# door_lock_controller.net
KiCad netlist of a schematic drawn in Altium Designer
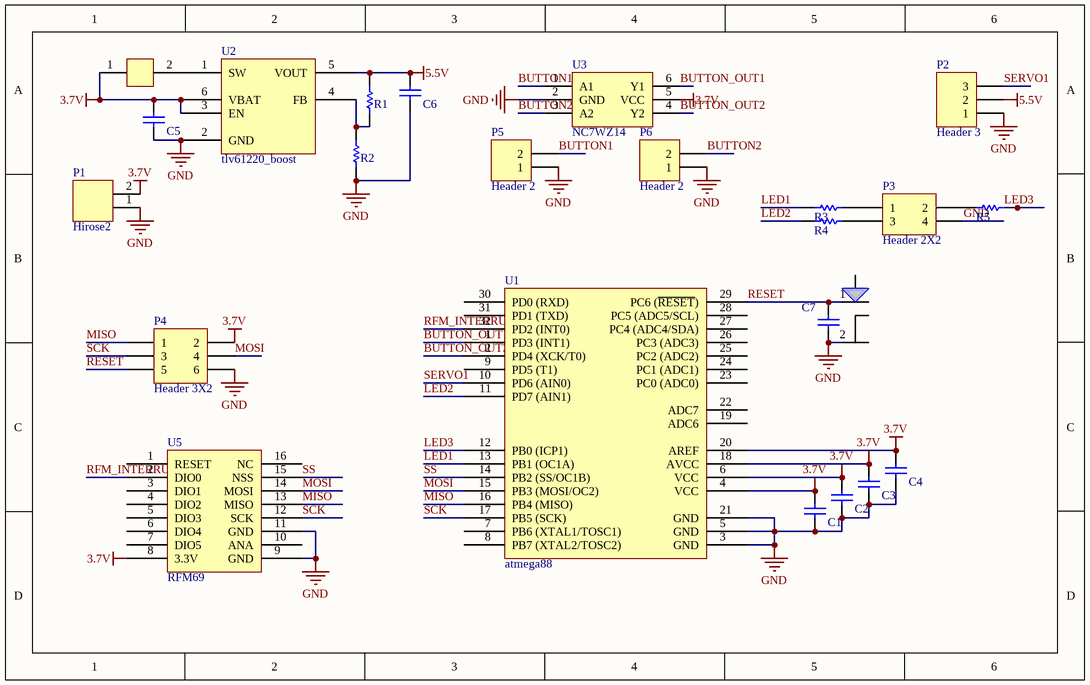
[diagram p0: door_lock_controller.SchDoc]

(export (version "E")
  (design (tool "Eeschema 10.0.6"))
  (components
    (comp (ref "C1")
      (value "CAP 100nF 10V 0603(1608)")
      (footprint "CAPC0603(1608)100_N")
      (description "CAP 100nF 10V ±20% 0603 (1608 Metric) Thickness 1mm SMD")
      (fields (field (name "TOLERANCE") "±20%"))
      (libsource (lib "Altium Content Vault") (part "CMP-1035-02581-1"))
    )
    (comp (ref "C2")
      (value "CAP 100nF 10V 0603(1608)")
      (footprint "CAPC0603(1608)100_N")
      (description "CAP 100nF 10V ±20% 0603 (1608 Metric) Thickness 1mm SMD")
      (fields (field (name "TOLERANCE") "±20%"))
      (libsource (lib "Altium Content Vault") (part "CMP-1035-02581-1"))
    )
    (comp (ref "C3")
      (value "CAP 100nF 10V 0603(1608)")
      (footprint "CAPC0603(1608)100_N")
      (description "CAP 100nF 10V ±20% 0603 (1608 Metric) Thickness 1mm SMD")
      (fields (field (name "TOLERANCE") "±20%"))
      (libsource (lib "Altium Content Vault") (part "CMP-1035-02581-1"))
    )
    (comp (ref "C4")
      (value "CAP 100nF 10V 0603(1608)")
      (footprint "CAPC0603(1608)100_N")
      (description "CAP 100nF 10V ±20% 0603 (1608 Metric) Thickness 1mm SMD")
      (fields (field (name "TOLERANCE") "±20%"))
      (libsource (lib "Altium Content Vault") (part "CMP-1035-02581-1"))
    )
    (comp (ref "C5")
      (value "CAP 10uF 10V 0603(1608)")
      (footprint "CAPC0603(1608)100_N")
      (description "CAP 10uF 10V ±10% 0603 (1608 Metric) Thickness 1mm SMD")
      (fields (field (name "TOLERANCE") "±10%"))
      (libsource (lib "Altium Content Vault") (part "CMP-1035-02799-1"))
    )
    (comp (ref "C6")
      (value "CAP 10uF 10V 0603(1608)")
      (footprint "CAPC0603(1608)100_N")
      (description "CAP 10uF 10V ±10% 0603 (1608 Metric) Thickness 1mm SMD")
      (fields (field (name "TOLERANCE") "±10%"))
      (libsource (lib "Altium Content Vault") (part "CMP-1035-02799-1"))
    )
    (comp (ref "C7")
      (value "CAP 10nF 10V 0603(1608)")
      (footprint "CAPC0603(1608)100_M")
      (description "CAP 10nF 10V ±2% 0603 (1608 Metric) Thickness 1mm SMD")
      (fields (field (name "TOLERANCE") "±2%"))
      (libsource (lib "Altium Content Vault") (part "CMP-1035-02304-1"))
    )
    (comp (ref "L1")
      (value "TYS6045_inductor")
      (footprint "TYS6045")
      (libsource (lib "Integrated_Library") (part "TYS6045_inductor"))
    )
    (comp (ref "P1")
      (value "Hirose2")
      (footprint "DF3A-2P-2DS")
      (libsource (lib "Integrated_Library") (part "Hirose2"))
    )
    (comp (ref "P2")
      (value "Header 3")
      (footprint "HDR1X3")
      (description "Header, 3-Pin")
      (fields (field (name "PUBLISHER") "Altium Limited"))
      (libsource (lib "Miscellaneous Connectors") (part "Header 3"))
    )
    (comp (ref "P3")
      (value "Header 2X2")
      (footprint "HDR2X2")
      (description "Header, 2-Pin, Dual row")
      (fields (field (name "PUBLISHER") "Altium Limited"))
      (libsource (lib "Miscellaneous Connectors") (part "Header 2X2"))
    )
    (comp (ref "P4")
      (value "Header 3X2")
      (footprint "HDR2X3")
      (description "Header, 3-Pin, Dual row")
      (fields (field (name "PUBLISHER") "Altium Limited"))
      (libsource (lib "Miscellaneous Connectors") (part "Header 3X2"))
    )
    (comp (ref "P5")
      (value "Header 2")
      (footprint "HDR1X2")
      (description "Header, 2-Pin")
      (fields (field (name "PUBLISHER") "Altium Limited"))
      (libsource (lib "Miscellaneous Connectors") (part "Header 2"))
    )
    (comp (ref "P6")
      (value "Header 2")
      (footprint "HDR1X2")
      (description "Header, 2-Pin")
      (fields (field (name "PUBLISHER") "Altium Limited"))
      (libsource (lib "Miscellaneous Connectors") (part "Header 2"))
    )
    (comp (ref "R1")
      (value "1M8 5% 0603(1608)")
      (footprint "RESC0603(1608)_L")
      (description "1M8 0.1W 5% 0603 (1608 Metric)  SMD")
      (fields (field (name "TOLERANCE") "5 %") (field (name "POWER") "0.1 W"))
      (libsource (lib "Altium Content Vault") (part "CMP-1012-00152-1"))
    )
    (comp (ref "R2")
      (value "180K 5% 0603(1608)")
      (footprint "RESC0603(1608)_L")
      (description "180K 0.1W 5% 0603 (1608 Metric)  SMD")
      (fields (field (name "POWER") "0.1 W") (field (name "TOLERANCE") "5 %"))
      (libsource (lib "Altium Content Vault") (part "CMP-1012-00128-1"))
    )
    (comp (ref "R3")
      (value "180R 5% 0603(1608)")
      (footprint "RESC0603(1608)_L")
      (description "180R 0.1W 5% 0603 (1608 Metric)  SMD")
      (fields (field (name "POWER") "0.1 W") (field (name "TOLERANCE") "5 %"))
      (libsource (lib "Altium Content Vault") (part "CMP-1012-00056-1"))
    )
    (comp (ref "R4")
      (value "180R 5% 0603(1608)")
      (footprint "RESC0603(1608)_L")
      (description "180R 0.1W 5% 0603 (1608 Metric)  SMD")
      (fields (field (name "POWER") "0.1 W") (field (name "TOLERANCE") "5 %"))
      (libsource (lib "Altium Content Vault") (part "CMP-1012-00056-1"))
    )
    (comp (ref "R5")
      (value "180R 5% 0603(1608)")
      (footprint "RESC0603(1608)_L")
      (description "180R 0.1W 5% 0603 (1608 Metric)  SMD")
      (fields (field (name "POWER") "0.1 W") (field (name "TOLERANCE") "5 %"))
      (libsource (lib "Altium Content Vault") (part "CMP-1012-00056-1"))
    )
    (comp (ref "S1")
      (value "2lead_low_profile_switch")
      (footprint "2lead_low_profile_switch")
      (libsource (lib "Integrated_Library") (part "2lead_low_profile_switch"))
    )
    (comp (ref "U1")
      (value "atmega88")
      (footprint "atmega44/88/168")
      (libsource (lib "Integrated_Library") (part "atmega88"))
    )
    (comp (ref "U2")
      (value "tlv61220_boost")
      (footprint "TLV61220_BOOST")
      (libsource (lib "Integrated_Library") (part "tlv61220_boost"))
    )
    (comp (ref "U3")
      (value "NC7WZ14")
      (footprint "NC7WZ14")
      (libsource (lib "Integrated_Library") (part "NC7WZ14"))
    )
    (comp (ref "U5")
      (value "RFM69")
      (footprint "RFM69")
      (libsource (lib "Integrated_Library") (part "RFM69"))
    )
  )
  (nets
    (net (code "1") (name "/BUTTON1") (class "Default")
      (node (ref "P5") (pin "2") (pinfunction "2_2") (pintype "passive"))
      (node (ref "U3") (pin "1") (pinfunction "A1_1") (pintype "passive"))
    )
    (net (code "2") (name "/BUTTON2") (class "Default")
      (node (ref "P6") (pin "2") (pinfunction "2_2") (pintype "passive"))
      (node (ref "U3") (pin "3") (pinfunction "A2_3") (pintype "passive"))
    )
    (net (code "3") (name "/BUTTON_OUT1") (class "Default")
      (node (ref "U1") (pin "1") (pinfunction "PD3_(INT1)_1") (pintype "passive"))
      (node (ref "U3") (pin "6") (pinfunction "Y1_6") (pintype "passive"))
    )
    (net (code "4") (name "/BUTTON_OUT2") (class "Default")
      (node (ref "U1") (pin "2") (pinfunction "PD4_(XCK/T0)_2") (pintype "passive"))
      (node (ref "U3") (pin "4") (pinfunction "Y2_4") (pintype "passive"))
    )
    (net (code "5") (name "/LED1") (class "Default")
      (node (ref "R3") (pin "1") (pinfunction "1_1") (pintype "passive"))
      (node (ref "U1") (pin "13") (pinfunction "PB1_(OC1A)_13") (pintype "passive"))
    )
    (net (code "6") (name "/LED2") (class "Default")
      (node (ref "R4") (pin "1") (pinfunction "1_1") (pintype "passive"))
      (node (ref "U1") (pin "11") (pinfunction "PD7_(AIN1)_11") (pintype "passive"))
    )
    (net (code "7") (name "/LED3") (class "Default")
      (node (ref "R5") (pin "2") (pinfunction "2_2") (pintype "passive"))
      (node (ref "U1") (pin "12") (pinfunction "PB0_(ICP1)_12") (pintype "passive"))
    )
    (net (code "8") (name "/MISO") (class "Default")
      (node (ref "P4") (pin "1") (pinfunction "1_1") (pintype "passive"))
      (node (ref "U1") (pin "16") (pinfunction "PB4_(MISO)_16") (pintype "passive"))
      (node (ref "U5") (pin "13") (pinfunction "MISO_13") (pintype "passive"))
    )
    (net (code "9") (name "/MOSI") (class "Default")
      (node (ref "P4") (pin "4") (pinfunction "4_4") (pintype "passive"))
      (node (ref "U1") (pin "15") (pinfunction "PB3_(MOSI/OC2)_15") (pintype "passive"))
      (node (ref "U5") (pin "14") (pinfunction "MOSI_14") (pintype "passive"))
    )
    (net (code "10") (name "/RESET") (class "Default")
      (node (ref "C7") (pin "2") (pinfunction "2_2") (pintype "passive"))
      (node (ref "P4") (pin "5") (pinfunction "5_5") (pintype "passive"))
      (node (ref "S1") (pin "1") (pinfunction "GND_1") (pintype "passive"))
      (node (ref "U1") (pin "29") (pinfunction "PC6_(~{RESET})_29") (pintype "passive"))
    )
    (net (code "11") (name "/RFM_INTERRUPT") (class "Default")
      (node (ref "U1") (pin "32") (pinfunction "PD2_(INT0)_32") (pintype "passive"))
      (node (ref "U5") (pin "2") (pinfunction "DIO0_2") (pintype "passive"))
    )
    (net (code "12") (name "/SCK") (class "Default")
      (node (ref "P4") (pin "3") (pinfunction "3_3") (pintype "passive"))
      (node (ref "U1") (pin "17") (pinfunction "PB5_(SCK)_17") (pintype "passive"))
      (node (ref "U5") (pin "12") (pinfunction "SCK_12") (pintype "passive"))
    )
    (net (code "13") (name "/SERVO1") (class "Default")
      (node (ref "P2") (pin "3") (pinfunction "3_3") (pintype "passive"))
      (node (ref "U1") (pin "10") (pinfunction "PD6_(AIN0)_10") (pintype "passive"))
    )
    (net (code "14") (name "/SS") (class "Default")
      (node (ref "U1") (pin "14") (pinfunction "PB2_(SS/OC1B)_14") (pintype "passive"))
      (node (ref "U5") (pin "15") (pinfunction "NSS_15") (pintype "passive"))
    )
    (net (code "15") (name "3.7V") (class "Default")
      (node (ref "C1") (pin "2") (pinfunction "2_2") (pintype "passive"))
      (node (ref "C2") (pin "2") (pinfunction "2_2") (pintype "passive"))
      (node (ref "C3") (pin "2") (pinfunction "2_2") (pintype "passive"))
      (node (ref "C4") (pin "2") (pinfunction "2_2") (pintype "passive"))
      (node (ref "C5") (pin "2") (pinfunction "2_2") (pintype "passive"))
      (node (ref "L1") (pin "1") (pintype "passive"))
      (node (ref "P1") (pin "2") (pintype "passive"))
      (node (ref "P4") (pin "2") (pinfunction "2_2") (pintype "passive"))
      (node (ref "U1") (pin "18") (pinfunction "AVCC_18") (pintype "passive"))
      (node (ref "U1") (pin "20") (pinfunction "AREF_20") (pintype "passive"))
      (node (ref "U1") (pin "4") (pinfunction "VCC_4") (pintype "passive"))
      (node (ref "U1") (pin "6") (pinfunction "VCC_6") (pintype "passive"))
      (node (ref "U2") (pin "3") (pinfunction "EN_3") (pintype "passive"))
      (node (ref "U2") (pin "6") (pinfunction "VBAT_6") (pintype "passive"))
      (node (ref "U3") (pin "5") (pinfunction "VCC_5") (pintype "passive"))
      (node (ref "U5") (pin "8") (pinfunction "3.3V_8") (pintype "passive"))
    )
    (net (code "16") (name "5.5V") (class "Default")
      (node (ref "C6") (pin "2") (pinfunction "2_2") (pintype "passive"))
      (node (ref "P2") (pin "2") (pinfunction "2_2") (pintype "passive"))
      (node (ref "R1") (pin "2") (pinfunction "2_2") (pintype "passive"))
      (node (ref "U2") (pin "5") (pinfunction "VOUT_5") (pintype "passive"))
    )
    (net (code "17") (name "GND") (class "Default")
      (node (ref "C1") (pin "1") (pinfunction "1_1") (pintype "passive"))
      (node (ref "C2") (pin "1") (pinfunction "1_1") (pintype "passive"))
      (node (ref "C3") (pin "1") (pinfunction "1_1") (pintype "passive"))
      (node (ref "C4") (pin "1") (pinfunction "1_1") (pintype "passive"))
      (node (ref "C5") (pin "1") (pinfunction "1_1") (pintype "passive"))
      (node (ref "C6") (pin "1") (pinfunction "1_1") (pintype "passive"))
      (node (ref "C7") (pin "1") (pinfunction "1_1") (pintype "passive"))
      (node (ref "P1") (pin "1") (pintype "passive"))
      (node (ref "P2") (pin "1") (pinfunction "1_1") (pintype "passive"))
      (node (ref "P3") (pin "4") (pinfunction "4_4") (pintype "passive"))
      (node (ref "P4") (pin "6") (pinfunction "6_6") (pintype "passive"))
      (node (ref "P5") (pin "1") (pinfunction "1_1") (pintype "passive"))
      (node (ref "P6") (pin "1") (pinfunction "1_1") (pintype "passive"))
      (node (ref "R2") (pin "1") (pinfunction "1_1") (pintype "passive"))
      (node (ref "S1") (pin "2") (pinfunction "GND_2") (pintype "passive"))
      (node (ref "U1") (pin "21") (pinfunction "GND_21") (pintype "passive"))
      (node (ref "U1") (pin "3") (pinfunction "GND_3") (pintype "passive"))
      (node (ref "U1") (pin "5") (pinfunction "GND_5") (pintype "passive"))
      (node (ref "U2") (pin "2") (pinfunction "GND_2") (pintype "passive"))
      (node (ref "U3") (pin "2") (pinfunction "GND_2") (pintype "passive"))
      (node (ref "U5") (pin "11") (pinfunction "GND_11") (pintype "passive"))
      (node (ref "U5") (pin "9") (pinfunction "GND_9") (pintype "passive"))
    )
    (net (code "18") (name "Net-(P3-Pad1)") (class "Default")
      (node (ref "P3") (pin "1") (pinfunction "1_1") (pintype "passive"))
      (node (ref "R3") (pin "2") (pinfunction "2_2") (pintype "passive"))
    )
    (net (code "19") (name "Net-(P3-Pad2)") (class "Default")
      (node (ref "P3") (pin "2") (pinfunction "2_2") (pintype "passive"))
      (node (ref "R5") (pin "1") (pinfunction "1_1") (pintype "passive"))
    )
    (net (code "20") (name "Net-(P3-Pad3)") (class "Default")
      (node (ref "P3") (pin "3") (pinfunction "3_3") (pintype "passive"))
      (node (ref "R4") (pin "2") (pinfunction "2_2") (pintype "passive"))
    )
    (net (code "21") (name "Net-(U2-FB)") (class "Default")
      (node (ref "R1") (pin "1") (pinfunction "1_1") (pintype "passive"))
      (node (ref "R2") (pin "2") (pinfunction "2_2") (pintype "passive"))
      (node (ref "U2") (pin "4") (pinfunction "FB_4") (pintype "passive"))
    )
    (net (code "22") (name "Net-(U2-SW)") (class "Default")
      (node (ref "L1") (pin "2") (pintype "passive"))
      (node (ref "U2") (pin "1") (pinfunction "SW_1") (pintype "passive"))
    )
    (net (code "23") (name "unconnected-(U1-ADC6-Pad19)") (class "Default")
      (node (ref "U1") (pin "19") (pinfunction "ADC6_19") (pintype "passive"))
    )
    (net (code "24") (name "unconnected-(U1-ADC7-Pad22)") (class "Default")
      (node (ref "U1") (pin "22") (pinfunction "ADC7_22") (pintype "passive"))
    )
    (net (code "25") (name "unconnected-(U1-PB6_(XTAL1{slash}TOSC1)-Pad7)") (class "Default")
      (node (ref "U1") (pin "7") (pinfunction "PB6_(XTAL1/TOSC1)_7") (pintype "passive"))
    )
    (net (code "26") (name "unconnected-(U1-PB7_(XTAL2{slash}TOSC2)-Pad8)") (class "Default")
      (node (ref "U1") (pin "8") (pinfunction "PB7_(XTAL2/TOSC2)_8") (pintype "passive"))
    )
    (net (code "27") (name "unconnected-(U1-PC0_(ADC0)-Pad23)") (class "Default")
      (node (ref "U1") (pin "23") (pinfunction "PC0_(ADC0)_23") (pintype "passive"))
    )
    (net (code "28") (name "unconnected-(U1-PC1_(ADC1)-Pad24)") (class "Default")
      (node (ref "U1") (pin "24") (pinfunction "PC1_(ADC1)_24") (pintype "passive"))
    )
    (net (code "29") (name "unconnected-(U1-PC2_(ADC2)-Pad25)") (class "Default")
      (node (ref "U1") (pin "25") (pinfunction "PC2_(ADC2)_25") (pintype "passive"))
    )
    (net (code "30") (name "unconnected-(U1-PC3_(ADC3)-Pad26)") (class "Default")
      (node (ref "U1") (pin "26") (pinfunction "PC3_(ADC3)_26") (pintype "passive"))
    )
    (net (code "31") (name "unconnected-(U1-PC4_(ADC4{slash}SDA)-Pad27)") (class "Default")
      (node (ref "U1") (pin "27") (pinfunction "PC4_(ADC4/SDA)_27") (pintype "passive"))
    )
    (net (code "32") (name "unconnected-(U1-PC5_(ADC5{slash}SCL)-Pad28)") (class "Default")
      (node (ref "U1") (pin "28") (pinfunction "PC5_(ADC5/SCL)_28") (pintype "passive"))
    )
    (net (code "33") (name "unconnected-(U1-PD0_(RXD)-Pad30)") (class "Default")
      (node (ref "U1") (pin "30") (pinfunction "PD0_(RXD)_30") (pintype "passive"))
    )
    (net (code "34") (name "unconnected-(U1-PD1_(TXD)-Pad31)") (class "Default")
      (node (ref "U1") (pin "31") (pinfunction "PD1_(TXD)_31") (pintype "passive"))
    )
    (net (code "35") (name "unconnected-(U1-PD5_(T1)-Pad9)") (class "Default")
      (node (ref "U1") (pin "9") (pinfunction "PD5_(T1)_9") (pintype "passive"))
    )
    (net (code "36") (name "unconnected-(U5-ANA-Pad10)") (class "Default")
      (node (ref "U5") (pin "10") (pinfunction "ANA_10") (pintype "passive"))
    )
    (net (code "37") (name "unconnected-(U5-DIO1-Pad3)") (class "Default")
      (node (ref "U5") (pin "3") (pinfunction "DIO1_3") (pintype "passive"))
    )
    (net (code "38") (name "unconnected-(U5-DIO2-Pad4)") (class "Default")
      (node (ref "U5") (pin "4") (pinfunction "DIO2_4") (pintype "passive"))
    )
    (net (code "39") (name "unconnected-(U5-DIO3-Pad5)") (class "Default")
      (node (ref "U5") (pin "5") (pinfunction "DIO3_5") (pintype "passive"))
    )
    (net (code "40") (name "unconnected-(U5-DIO4-Pad6)") (class "Default")
      (node (ref "U5") (pin "6") (pinfunction "DIO4_6") (pintype "passive"))
    )
    (net (code "41") (name "unconnected-(U5-DIO5-Pad7)") (class "Default")
      (node (ref "U5") (pin "7") (pinfunction "DIO5_7") (pintype "passive"))
    )
    (net (code "42") (name "unconnected-(U5-NC-Pad16)") (class "Default")
      (node (ref "U5") (pin "16") (pinfunction "NC_16") (pintype "passive"))
    )
    (net (code "43") (name "unconnected-(U5-RESET-Pad1)") (class "Default")
      (node (ref "U5") (pin "1") (pinfunction "RESET_1") (pintype "passive"))
    )
  )
)
